# IO.net
KiCad netlist of a schematic drawn in Altium Designer
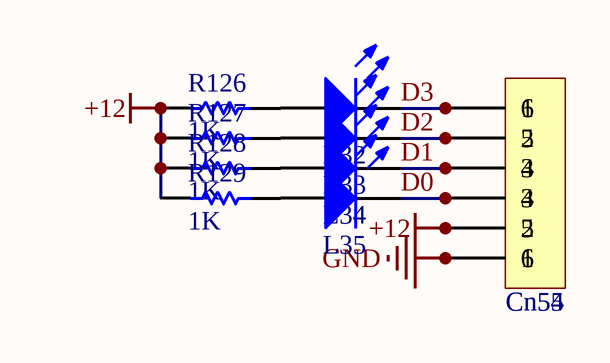
[diagram p0: IO模組燈.SchDoc]

(export (version "E")
  (design (tool "Eeschema 10.0.6"))
  (components
    (comp (ref "Cn54")
      (value "KF2510-6")
      (footprint "Connector_KF2510-6A")
      (description "接線端子")
      (libsource (lib "MyLibray") (part "Contact(6P)"))
    )
    (comp (ref "Cn55")
      (value "KF2510-6")
      (footprint "Connector_KF2510-6A")
      (description "接線端子")
      (libsource (lib "") (part "Contact(6P)_1"))
    )
    (comp (ref "L32")
      (value "藍")
      (footprint "LED-1206")
      (description "LED")
      (libsource (lib "MyLibray") (part "LED"))
    )
    (comp (ref "L33")
      (value "藍")
      (footprint "LED-1206")
      (description "LED")
      (libsource (lib "MyLibray") (part "LED"))
    )
    (comp (ref "L34")
      (value "藍")
      (footprint "LED-1206")
      (description "LED")
      (libsource (lib "MyLibray") (part "LED"))
    )
    (comp (ref "L35")
      (value "藍")
      (footprint "LED-1206")
      (description "LED")
      (libsource (lib "MyLibray") (part "LED"))
    )
    (comp (ref "R126")
      (value "1K")
      (footprint "Res-1206")
      (description "電阻")
      (libsource (lib "MyLibray") (part "Res"))
    )
    (comp (ref "R127")
      (value "1K")
      (footprint "Res-1206")
      (description "電阻")
      (libsource (lib "MyLibray") (part "Res"))
    )
    (comp (ref "R128")
      (value "1K")
      (footprint "Res-1206")
      (description "電阻")
      (libsource (lib "MyLibray") (part "Res"))
    )
    (comp (ref "R129")
      (value "1K")
      (footprint "Res-1206")
      (description "電阻")
      (libsource (lib "MyLibray") (part "Res"))
    )
  )
  (nets
    (net (code "1") (name "+12") (class "Default")
      (node (ref "Cn54") (pin "5") (pinfunction "5_5") (pintype "passive"))
      (node (ref "Cn55") (pin "2") (pinfunction "2_2") (pintype "passive"))
      (node (ref "R126") (pin "2") (pinfunction "2_2") (pintype "passive"))
      (node (ref "R127") (pin "2") (pinfunction "2_2") (pintype "passive"))
      (node (ref "R128") (pin "2") (pinfunction "2_2") (pintype "passive"))
      (node (ref "R129") (pin "2") (pinfunction "2_2") (pintype "passive"))
    )
    (net (code "2") (name "/D0") (class "Default")
      (node (ref "Cn54") (pin "4") (pinfunction "4_4") (pintype "passive"))
      (node (ref "Cn55") (pin "3") (pinfunction "3_3") (pintype "passive"))
      (node (ref "L35") (pin "1") (pinfunction "K_1") (pintype "passive"))
    )
    (net (code "3") (name "/D1") (class "Default")
      (node (ref "Cn54") (pin "3") (pinfunction "3_3") (pintype "passive"))
      (node (ref "Cn55") (pin "4") (pinfunction "4_4") (pintype "passive"))
      (node (ref "L34") (pin "1") (pinfunction "K_1") (pintype "passive"))
    )
    (net (code "4") (name "/D2") (class "Default")
      (node (ref "Cn54") (pin "2") (pinfunction "2_2") (pintype "passive"))
      (node (ref "Cn55") (pin "5") (pinfunction "5_5") (pintype "passive"))
      (node (ref "L33") (pin "1") (pinfunction "K_1") (pintype "passive"))
    )
    (net (code "5") (name "/D3") (class "Default")
      (node (ref "Cn54") (pin "1") (pinfunction "1_1") (pintype "passive"))
      (node (ref "Cn55") (pin "6") (pinfunction "6_6") (pintype "passive"))
      (node (ref "L32") (pin "1") (pinfunction "K_1") (pintype "passive"))
    )
    (net (code "6") (name "GND") (class "Default")
      (node (ref "Cn54") (pin "6") (pinfunction "6_6") (pintype "passive"))
      (node (ref "Cn55") (pin "1") (pinfunction "1_1") (pintype "passive"))
    )
    (net (code "7") (name "Net-(L32-A)") (class "Default")
      (node (ref "L32") (pin "2") (pinfunction "A_2") (pintype "passive"))
      (node (ref "R126") (pin "1") (pinfunction "1_1") (pintype "passive"))
    )
    (net (code "8") (name "Net-(L33-A)") (class "Default")
      (node (ref "L33") (pin "2") (pinfunction "A_2") (pintype "passive"))
      (node (ref "R127") (pin "1") (pinfunction "1_1") (pintype "passive"))
    )
    (net (code "9") (name "Net-(L34-A)") (class "Default")
      (node (ref "L34") (pin "2") (pinfunction "A_2") (pintype "passive"))
      (node (ref "R128") (pin "1") (pinfunction "1_1") (pintype "passive"))
    )
    (net (code "10") (name "Net-(L35-A)") (class "Default")
      (node (ref "L35") (pin "2") (pinfunction "A_2") (pintype "passive"))
      (node (ref "R129") (pin "1") (pinfunction "1_1") (pintype "passive"))
    )
  )
)
